# USB_LEDs.net
KiCad netlist of a schematic drawn in EAGLE
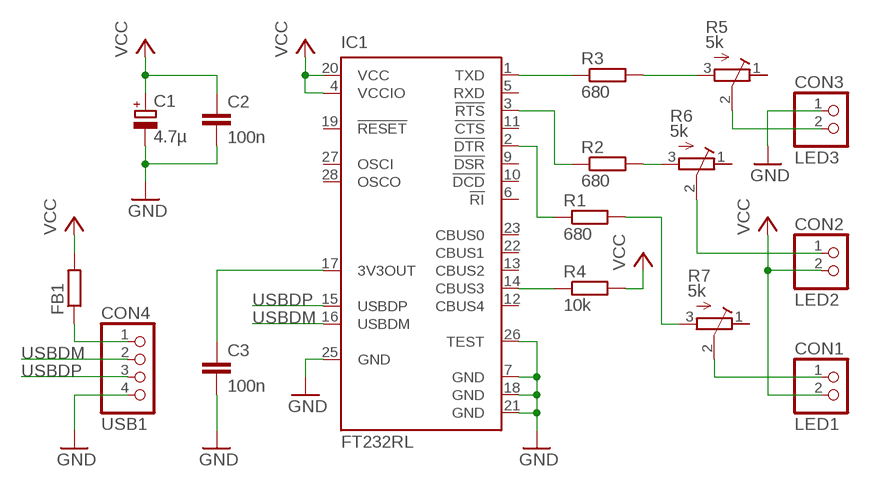
[diagram p0: schematic, sheet 1]

(export (version "E")
  (design (tool "Eeschema 10.0.6"))
  (components
    (comp (ref "C1")
      (value "4.7µ")
      (footprint "eagle-import:R_2012-12R")
      (libsource (lib "eagle-import") (part "CPOL-EUR/2012-12R"))
    )
    (comp (ref "C2")
      (value "100n")
      (footprint "eagle-import:C0805")
      (libsource (lib "eagle-import") (part "C-EUC0805"))
    )
    (comp (ref "C3")
      (value "100n")
      (footprint "eagle-import:C0805")
      (libsource (lib "eagle-import") (part "C-EUC0805"))
    )
    (comp (ref "CON1")
      (value "LED1")
      (footprint "eagle-import:1X02")
      (libsource (lib "eagle-import") (part "PINHD-1X2"))
    )
    (comp (ref "CON2")
      (value "LED2")
      (footprint "eagle-import:1X02")
      (libsource (lib "eagle-import") (part "PINHD-1X2"))
    )
    (comp (ref "CON3")
      (value "LED3")
      (footprint "eagle-import:1X02")
      (libsource (lib "eagle-import") (part "PINHD-1X2"))
    )
    (comp (ref "CON4")
      (value "USB1")
      (footprint "eagle-import:1X04")
      (libsource (lib "eagle-import") (part "PINHD-1X4"))
    )
    (comp (ref "FB1")
      (value "R-EU_R0805")
      (footprint "eagle-import:R0805")
      (libsource (lib "eagle-import") (part "R-EU_R0805"))
    )
    (comp (ref "IC1")
      (value "FT232RL")
      (footprint "eagle-import:SSOP28")
      (libsource (lib "eagle-import") (part "FT232RL"))
    )
    (comp (ref "R1")
      (value "680")
      (footprint "eagle-import:R0805")
      (libsource (lib "eagle-import") (part "R-EU_R0805"))
    )
    (comp (ref "R2")
      (value "680")
      (footprint "eagle-import:R0805")
      (libsource (lib "eagle-import") (part "R-EU_R0805"))
    )
    (comp (ref "R3")
      (value "680")
      (footprint "eagle-import:R0805")
      (libsource (lib "eagle-import") (part "R-EU_R0805"))
    )
    (comp (ref "R4")
      (value "10k")
      (footprint "eagle-import:R0805")
      (libsource (lib "eagle-import") (part "R-EU_R0805"))
    )
    (comp (ref "R5")
      (value "5k")
      (footprint "eagle-import:RTRIM3314J")
      (libsource (lib "eagle-import") (part "R-TRIMM3314J"))
    )
    (comp (ref "R6")
      (value "5k")
      (footprint "eagle-import:RTRIM3314J")
      (libsource (lib "eagle-import") (part "R-TRIMM3314J"))
    )
    (comp (ref "R7")
      (value "5k")
      (footprint "eagle-import:RTRIM3314J")
      (libsource (lib "eagle-import") (part "R-TRIMM3314J"))
    )
  )
  (nets
    (net (code "1") (name "/USBDM") (class "Default")
      (node (ref "CON4") (pin "2") (pinfunction "2_2") (pintype "passive"))
      (node (ref "IC1") (pin "16") (pinfunction "USBDM_16") (pintype "bidirectional"))
    )
    (net (code "2") (name "/USBDP") (class "Default")
      (node (ref "CON4") (pin "3") (pinfunction "3_3") (pintype "passive"))
      (node (ref "IC1") (pin "15") (pinfunction "USBDP_15") (pintype "bidirectional"))
    )
    (net (code "3") (name "GND") (class "Default")
      (node (ref "C1") (pin "-") (pinfunction "-_-") (pintype "passive"))
      (node (ref "C2") (pin "2") (pinfunction "2_2") (pintype "passive"))
      (node (ref "C3") (pin "2") (pinfunction "2_2") (pintype "passive"))
      (node (ref "CON3") (pin "1") (pinfunction "1_1") (pintype "passive"))
      (node (ref "CON4") (pin "4") (pinfunction "4_4") (pintype "passive"))
      (node (ref "IC1") (pin "18") (pinfunction "GND_18") (pintype "power_in"))
      (node (ref "IC1") (pin "21") (pinfunction "GND_21") (pintype "power_in"))
      (node (ref "IC1") (pin "25") (pinfunction "GND_25") (pintype "power_in"))
      (node (ref "IC1") (pin "26") (pinfunction "TEST_26") (pintype "input"))
      (node (ref "IC1") (pin "7") (pinfunction "GND_7") (pintype "power_in"))
    )
    (net (code "4") (name "Net-(CON4-Pad1)") (class "Default")
      (node (ref "CON4") (pin "1") (pinfunction "1_1") (pintype "passive"))
      (node (ref "FB1") (pin "1") (pinfunction "1_1") (pintype "passive"))
    )
    (net (code "5") (name "Net-(IC1-3V3OUT)") (class "Default")
      (node (ref "C3") (pin "1") (pinfunction "1_1") (pintype "passive"))
      (node (ref "IC1") (pin "17") (pinfunction "3V3OUT_17") (pintype "output"))
    )
    (net (code "6") (name "Net-(IC1-CBUS3)") (class "Default")
      (node (ref "IC1") (pin "14") (pinfunction "CBUS3_14") (pintype "bidirectional"))
      (node (ref "R4") (pin "1") (pinfunction "1_1") (pintype "passive"))
    )
    (net (code "7") (name "Net-(IC1-TXD)") (class "Default")
      (node (ref "IC1") (pin "1") (pinfunction "TXD_1") (pintype "output"))
      (node (ref "R3") (pin "1") (pinfunction "1_1") (pintype "passive"))
    )
    (net (code "8") (name "Net-(IC1-~{DTR})") (class "Default")
      (node (ref "IC1") (pin "2") (pinfunction "~{DTR}_2") (pintype "output"))
      (node (ref "R1") (pin "1") (pinfunction "1_1") (pintype "passive"))
    )
    (net (code "9") (name "Net-(IC1-~{RTS})") (class "Default")
      (node (ref "IC1") (pin "3") (pinfunction "~{RTS}_3") (pintype "output"))
      (node (ref "R2") (pin "1") (pinfunction "1_1") (pintype "passive"))
    )
    (net (code "10") (name "Net-(R5-A)") (class "Default")
      (node (ref "R3") (pin "2") (pinfunction "2_2") (pintype "passive"))
      (node (ref "R5") (pin "3") (pinfunction "A_3") (pintype "passive"))
    )
    (net (code "11") (name "Net-(R5-S)") (class "Default")
      (node (ref "CON3") (pin "2") (pinfunction "2_2") (pintype "passive"))
      (node (ref "R5") (pin "2") (pinfunction "S_2") (pintype "passive"))
    )
    (net (code "12") (name "Net-(R6-A)") (class "Default")
      (node (ref "R2") (pin "2") (pinfunction "2_2") (pintype "passive"))
      (node (ref "R6") (pin "3") (pinfunction "A_3") (pintype "passive"))
    )
    (net (code "13") (name "Net-(R6-S)") (class "Default")
      (node (ref "CON2") (pin "1") (pinfunction "1_1") (pintype "passive"))
      (node (ref "R6") (pin "2") (pinfunction "S_2") (pintype "passive"))
    )
    (net (code "14") (name "Net-(R7-A)") (class "Default")
      (node (ref "R1") (pin "2") (pinfunction "2_2") (pintype "passive"))
      (node (ref "R7") (pin "3") (pinfunction "A_3") (pintype "passive"))
    )
    (net (code "15") (name "Net-(R7-S)") (class "Default")
      (node (ref "CON1") (pin "1") (pinfunction "1_1") (pintype "passive"))
      (node (ref "R7") (pin "2") (pinfunction "S_2") (pintype "passive"))
    )
    (net (code "16") (name "VCC") (class "Default")
      (node (ref "C1") (pin "+") (pinfunction "+_+") (pintype "passive"))
      (node (ref "C2") (pin "1") (pinfunction "1_1") (pintype "passive"))
      (node (ref "CON1") (pin "2") (pinfunction "2_2") (pintype "passive"))
      (node (ref "CON2") (pin "2") (pinfunction "2_2") (pintype "passive"))
      (node (ref "FB1") (pin "2") (pinfunction "2_2") (pintype "passive"))
      (node (ref "IC1") (pin "20") (pinfunction "VCC_20") (pintype "power_in"))
      (node (ref "IC1") (pin "4") (pinfunction "VCCIO_4") (pintype "power_in"))
      (node (ref "R4") (pin "2") (pinfunction "2_2") (pintype "passive"))
    )
    (net (code "17") (name "unconnected-(IC1-CBUS0-Pad23)") (class "Default")
      (node (ref "IC1") (pin "23") (pinfunction "CBUS0_23") (pintype "bidirectional"))
    )
    (net (code "18") (name "unconnected-(IC1-CBUS1-Pad22)") (class "Default")
      (node (ref "IC1") (pin "22") (pinfunction "CBUS1_22") (pintype "bidirectional"))
    )
    (net (code "19") (name "unconnected-(IC1-CBUS2-Pad13)") (class "Default")
      (node (ref "IC1") (pin "13") (pinfunction "CBUS2_13") (pintype "bidirectional"))
    )
    (net (code "20") (name "unconnected-(IC1-CBUS4-Pad12)") (class "Default")
      (node (ref "IC1") (pin "12") (pinfunction "CBUS4_12") (pintype "bidirectional"))
    )
    (net (code "21") (name "unconnected-(IC1-OSCI-Pad27)") (class "Default")
      (node (ref "IC1") (pin "27") (pinfunction "OSCI_27") (pintype "input"))
    )
    (net (code "22") (name "unconnected-(IC1-OSCO-Pad28)") (class "Default")
      (node (ref "IC1") (pin "28") (pinfunction "OSCO_28") (pintype "output"))
    )
    (net (code "23") (name "unconnected-(IC1-RXD-Pad5)") (class "Default")
      (node (ref "IC1") (pin "5") (pinfunction "RXD_5") (pintype "input"))
    )
    (net (code "24") (name "unconnected-(IC1-~{CTS}-Pad11)") (class "Default")
      (node (ref "IC1") (pin "11") (pinfunction "~{CTS}_11") (pintype "input"))
    )
    (net (code "25") (name "unconnected-(IC1-~{DCD}-Pad10)") (class "Default")
      (node (ref "IC1") (pin "10") (pinfunction "~{DCD}_10") (pintype "input"))
    )
    (net (code "26") (name "unconnected-(IC1-~{DSR}-Pad9)") (class "Default")
      (node (ref "IC1") (pin "9") (pinfunction "~{DSR}_9") (pintype "input"))
    )
    (net (code "27") (name "unconnected-(IC1-~{RESET}-Pad19)") (class "Default")
      (node (ref "IC1") (pin "19") (pinfunction "~{RESET}_19") (pintype "input"))
    )
    (net (code "28") (name "unconnected-(IC1-~{RI}-Pad6)") (class "Default")
      (node (ref "IC1") (pin "6") (pinfunction "~{RI}_6") (pintype "input"))
    )
    (net (code "29") (name "unconnected-(R5-E-Pad1)") (class "Default")
      (node (ref "R5") (pin "1") (pinfunction "E_1") (pintype "passive"))
    )
    (net (code "30") (name "unconnected-(R6-E-Pad1)") (class "Default")
      (node (ref "R6") (pin "1") (pinfunction "E_1") (pintype "passive"))
    )
    (net (code "31") (name "unconnected-(R7-E-Pad1)") (class "Default")
      (node (ref "R7") (pin "1") (pinfunction "E_1") (pintype "passive"))
    )
  )
)
